# namcogunpcb.net
KiCad netlist of a schematic drawn in EAGLE
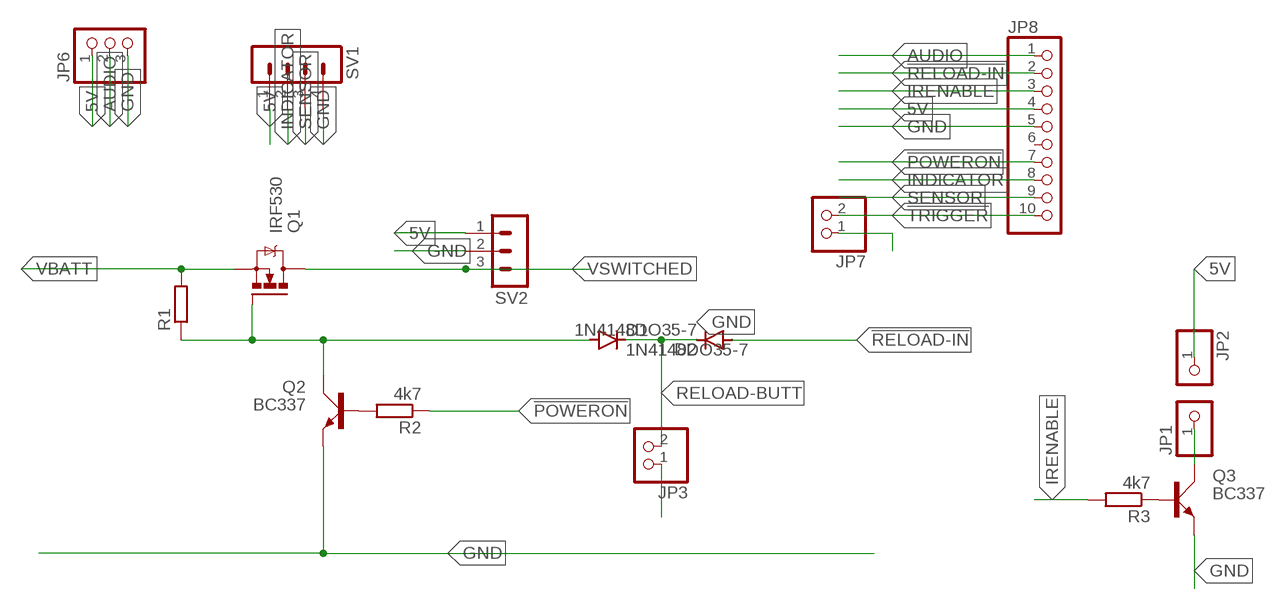
[diagram p0: schematic, sheet 1]

(export (version "E")
  (design (tool "Eeschema 10.0.6"))
  (components
    (comp (ref "D1")
      (value "1N4148DO35-7")
      (footprint "eagle-import:DO35-7")
      (libsource (lib "eagle-import") (part "1N4148DO35-7"))
    )
    (comp (ref "D2")
      (value "1N4148DO35-7")
      (footprint "eagle-import:DO35-7")
      (libsource (lib "eagle-import") (part "1N4148DO35-7"))
    )
    (comp (ref "JP1")
      (value "PINHD-1X1")
      (footprint "eagle-import:1X01")
      (libsource (lib "eagle-import") (part "PINHD-1X1"))
    )
    (comp (ref "JP2")
      (value "PINHD-1X1")
      (footprint "eagle-import:1X01")
      (libsource (lib "eagle-import") (part "PINHD-1X1"))
    )
    (comp (ref "JP3")
      (value "PINHD-1X2")
      (footprint "eagle-import:1X02")
      (libsource (lib "eagle-import") (part "PINHD-1X2"))
    )
    (comp (ref "JP6")
      (value "PINHD-1X3")
      (footprint "eagle-import:1X03")
      (libsource (lib "eagle-import") (part "PINHD-1X3"))
    )
    (comp (ref "JP7")
      (value "PINHD-1X2")
      (footprint "eagle-import:1X02")
      (libsource (lib "eagle-import") (part "PINHD-1X2"))
    )
    (comp (ref "JP8")
      (value "PINHD-1X10")
      (footprint "eagle-import:1X10")
      (libsource (lib "eagle-import") (part "PINHD-1X10"))
    )
    (comp (ref "Q1")
      (value "IRF530")
      (footprint "eagle-import:TO220BV")
      (libsource (lib "eagle-import") (part "IRF530"))
    )
    (comp (ref "Q2")
      (value "BC337")
      (footprint "eagle-import:SOT54A")
      (libsource (lib "eagle-import") (part "BC337"))
    )
    (comp (ref "Q3")
      (value "BC337")
      (footprint "eagle-import:SOT54A")
      (libsource (lib "eagle-import") (part "BC337"))
    )
    (comp (ref "R1")
      (value "R-EU_0207/10")
      (footprint "eagle-import:0207_10")
      (libsource (lib "eagle-import") (part "R-EU_0207/10"))
    )
    (comp (ref "R2")
      (value "4k7")
      (footprint "eagle-import:0207_10")
      (libsource (lib "eagle-import") (part "R-EU_0207/10"))
    )
    (comp (ref "R3")
      (value "4k7")
      (footprint "eagle-import:0207_10")
      (libsource (lib "eagle-import") (part "R-EU_0207/10"))
    )
    (comp (ref "SV1")
      (value "MA04-1")
      (footprint "eagle-import:MA04-1")
      (libsource (lib "eagle-import") (part "MA04-1"))
    )
    (comp (ref "SV2")
      (value "MA03-1")
      (footprint "eagle-import:MA03-1")
      (libsource (lib "eagle-import") (part "MA03-1"))
    )
  )
  (nets
    (net (code "1") (name "/~{POWERON}") (class "Default")
      (node (ref "JP8") (pin "7") (pinfunction "7_7") (pintype "passive"))
      (node (ref "R2") (pin "1") (pinfunction "1_1") (pintype "passive"))
    )
    (net (code "2") (name "/~{RELOAD-IN}") (class "Default")
      (node (ref "D2") (pin "A") (pinfunction "A_A") (pintype "passive"))
      (node (ref "JP8") (pin "2") (pinfunction "2_2") (pintype "passive"))
    )
    (net (code "3") (name "/~{TRIGGER}") (class "Default")
      (node (ref "JP7") (pin "2") (pinfunction "2_2") (pintype "passive"))
      (node (ref "JP8") (pin "10") (pinfunction "10_10") (pintype "passive"))
    )
    (net (code "4") (name "5V") (class "Default")
      (node (ref "JP2") (pin "1") (pinfunction "1_1") (pintype "passive"))
      (node (ref "JP6") (pin "1") (pinfunction "1_1") (pintype "passive"))
      (node (ref "JP8") (pin "4") (pinfunction "4_4") (pintype "passive"))
      (node (ref "SV1") (pin "1") (pinfunction "1_1") (pintype "passive"))
      (node (ref "SV2") (pin "1") (pinfunction "1_1") (pintype "passive"))
    )
    (net (code "5") (name "AUDIO") (class "Default")
      (node (ref "JP6") (pin "2") (pinfunction "2_2") (pintype "passive"))
      (node (ref "JP8") (pin "1") (pinfunction "1_1") (pintype "passive"))
    )
    (net (code "6") (name "GND") (class "Default")
      (node (ref "JP3") (pin "1") (pinfunction "1_1") (pintype "passive"))
      (node (ref "JP6") (pin "3") (pinfunction "3_3") (pintype "passive"))
      (node (ref "JP7") (pin "1") (pinfunction "1_1") (pintype "passive"))
      (node (ref "JP8") (pin "5") (pinfunction "5_5") (pintype "passive"))
      (node (ref "Q2") (pin "E") (pinfunction "E_E") (pintype "passive"))
      (node (ref "Q3") (pin "E") (pinfunction "E_E") (pintype "passive"))
      (node (ref "SV1") (pin "4") (pinfunction "4_4") (pintype "passive"))
      (node (ref "SV2") (pin "2") (pinfunction "2_2") (pintype "passive"))
    )
    (net (code "7") (name "INDICATOR") (class "Default")
      (node (ref "JP8") (pin "8") (pinfunction "8_8") (pintype "passive"))
      (node (ref "SV1") (pin "2") (pinfunction "2_2") (pintype "passive"))
    )
    (net (code "8") (name "IRENABLE") (class "Default")
      (node (ref "JP8") (pin "3") (pinfunction "3_3") (pintype "passive"))
      (node (ref "R3") (pin "2") (pinfunction "2_2") (pintype "passive"))
    )
    (net (code "9") (name "Net-(D1-PadA)") (class "Default")
      (node (ref "D1") (pin "A") (pinfunction "A_A") (pintype "passive"))
      (node (ref "Q1") (pin "G") (pinfunction "G_G") (pintype "passive"))
      (node (ref "Q2") (pin "C") (pinfunction "C_C") (pintype "passive"))
      (node (ref "R1") (pin "1") (pinfunction "1_1") (pintype "passive"))
    )
    (net (code "10") (name "Net-(JP1-Pad1)") (class "Default")
      (node (ref "JP1") (pin "1") (pinfunction "1_1") (pintype "passive"))
      (node (ref "Q3") (pin "C") (pinfunction "C_C") (pintype "passive"))
    )
    (net (code "11") (name "Net-(Q2-PadB)") (class "Default")
      (node (ref "Q2") (pin "B") (pinfunction "B_B") (pintype "passive"))
      (node (ref "R2") (pin "2") (pinfunction "2_2") (pintype "passive"))
    )
    (net (code "12") (name "Net-(Q3-PadB)") (class "Default")
      (node (ref "Q3") (pin "B") (pinfunction "B_B") (pintype "passive"))
      (node (ref "R3") (pin "1") (pinfunction "1_1") (pintype "passive"))
    )
    (net (code "13") (name "RELOAD-BUTT") (class "Default")
      (node (ref "D1") (pin "C") (pinfunction "C_C") (pintype "passive"))
      (node (ref "D2") (pin "C") (pinfunction "C_C") (pintype "passive"))
      (node (ref "JP3") (pin "2") (pinfunction "2_2") (pintype "passive"))
    )
    (net (code "14") (name "SENSOR") (class "Default")
      (node (ref "JP8") (pin "9") (pinfunction "9_9") (pintype "passive"))
      (node (ref "SV1") (pin "3") (pinfunction "3_3") (pintype "passive"))
    )
    (net (code "15") (name "VBATT") (class "Default")
      (node (ref "Q1") (pin "S") (pinfunction "S_S") (pintype "passive"))
      (node (ref "R1") (pin "2") (pinfunction "2_2") (pintype "passive"))
    )
    (net (code "16") (name "VSWITCHED") (class "Default")
      (node (ref "Q1") (pin "D") (pinfunction "D_D") (pintype "passive"))
      (node (ref "SV2") (pin "3") (pinfunction "3_3") (pintype "passive"))
    )
    (net (code "17") (name "unconnected-(JP8-Pad6)") (class "Default")
      (node (ref "JP8") (pin "6") (pinfunction "6_6") (pintype "passive"))
    )
  )
)
